# record.net
KiCad netlist of a schematic drawn in EAGLE
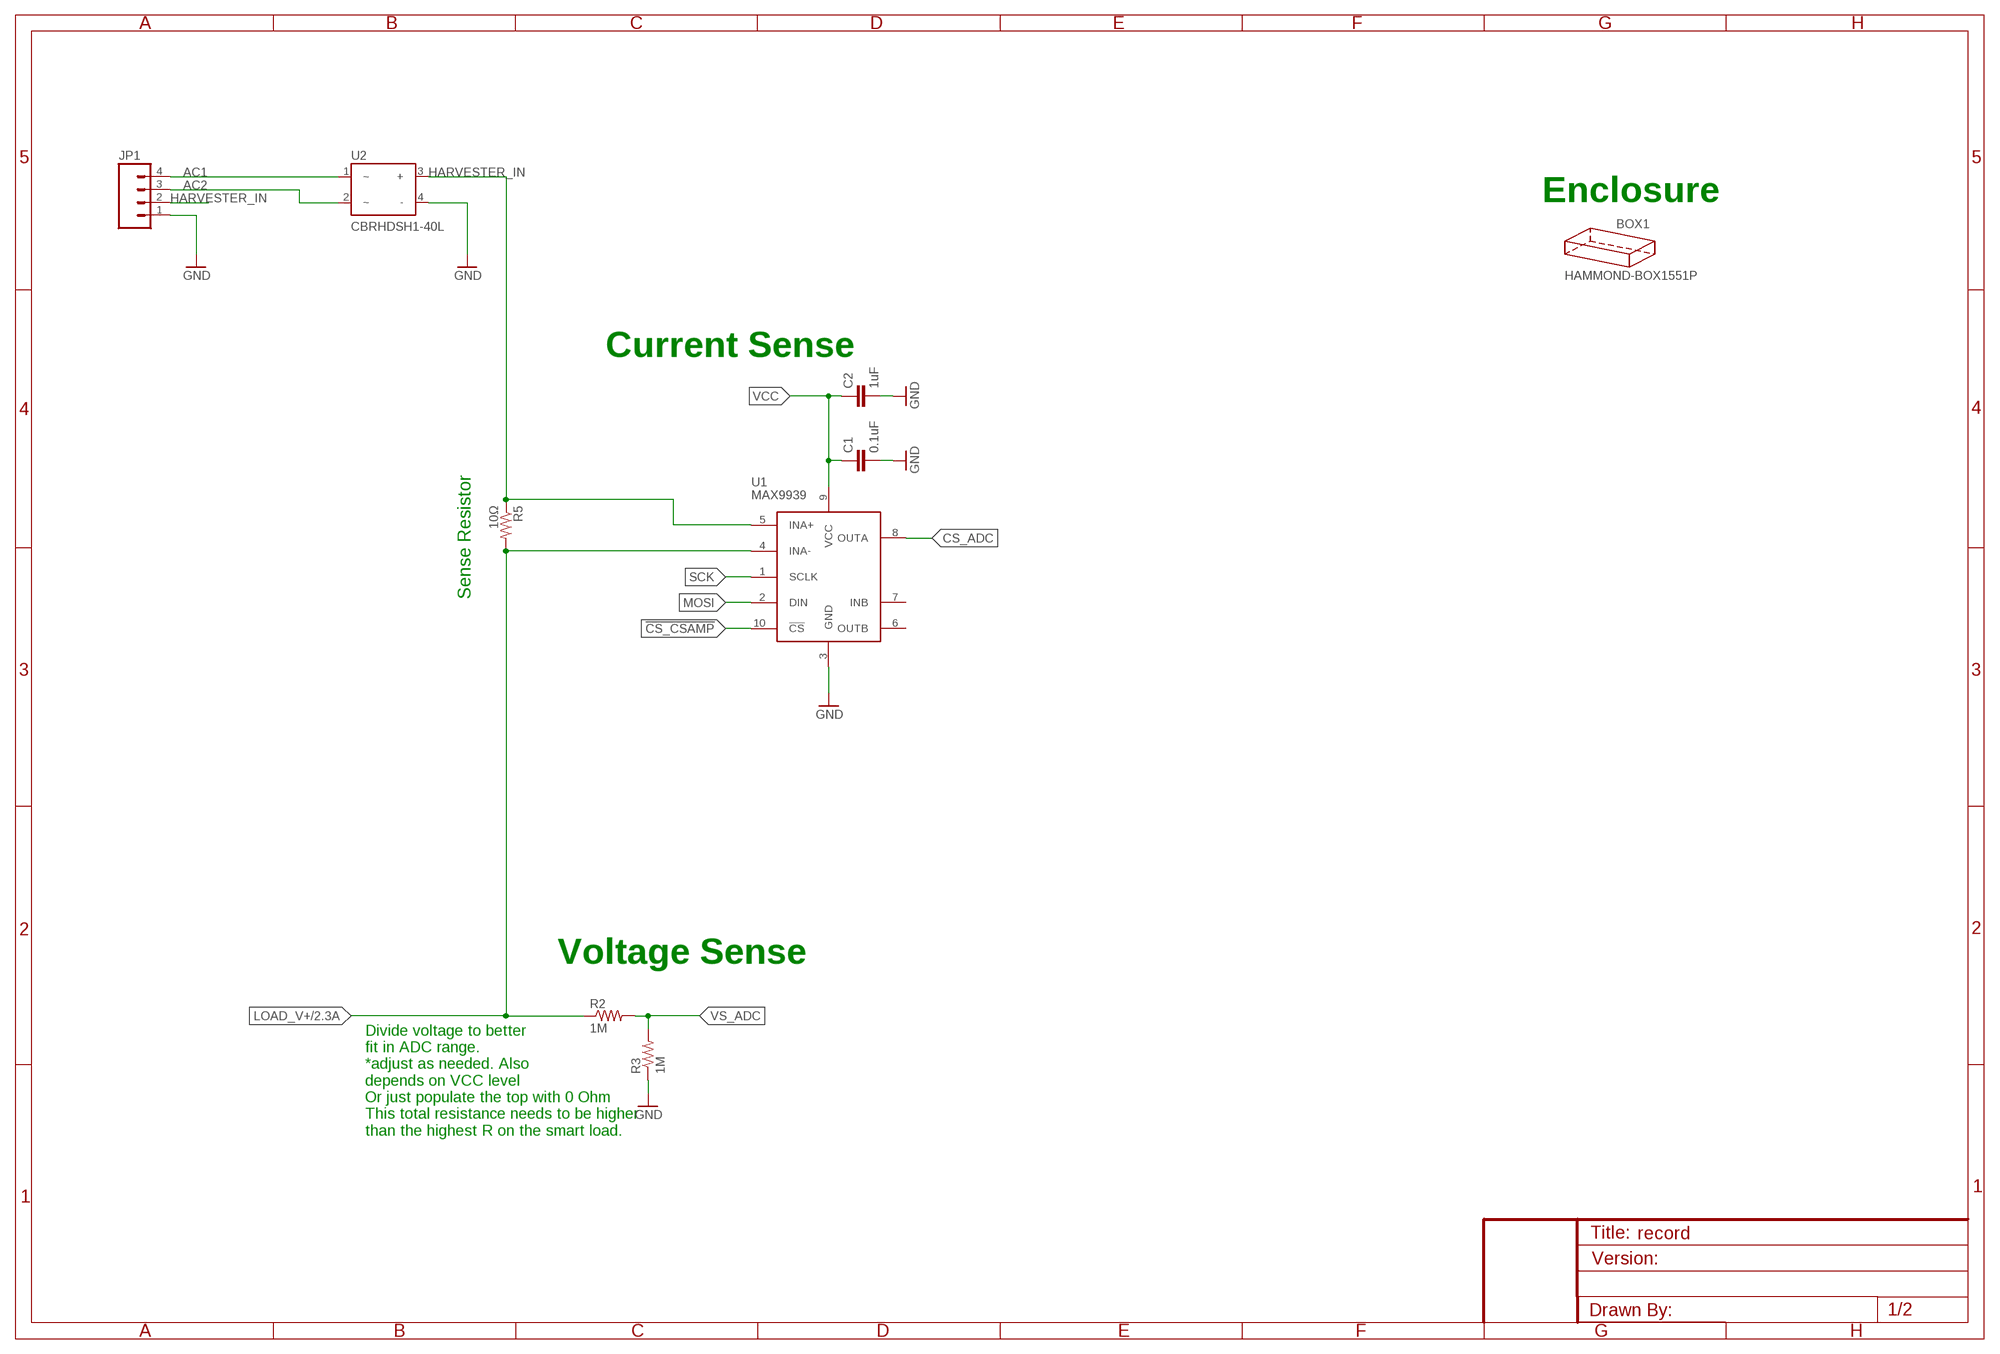
[diagram p0: schematic, sheet 1]
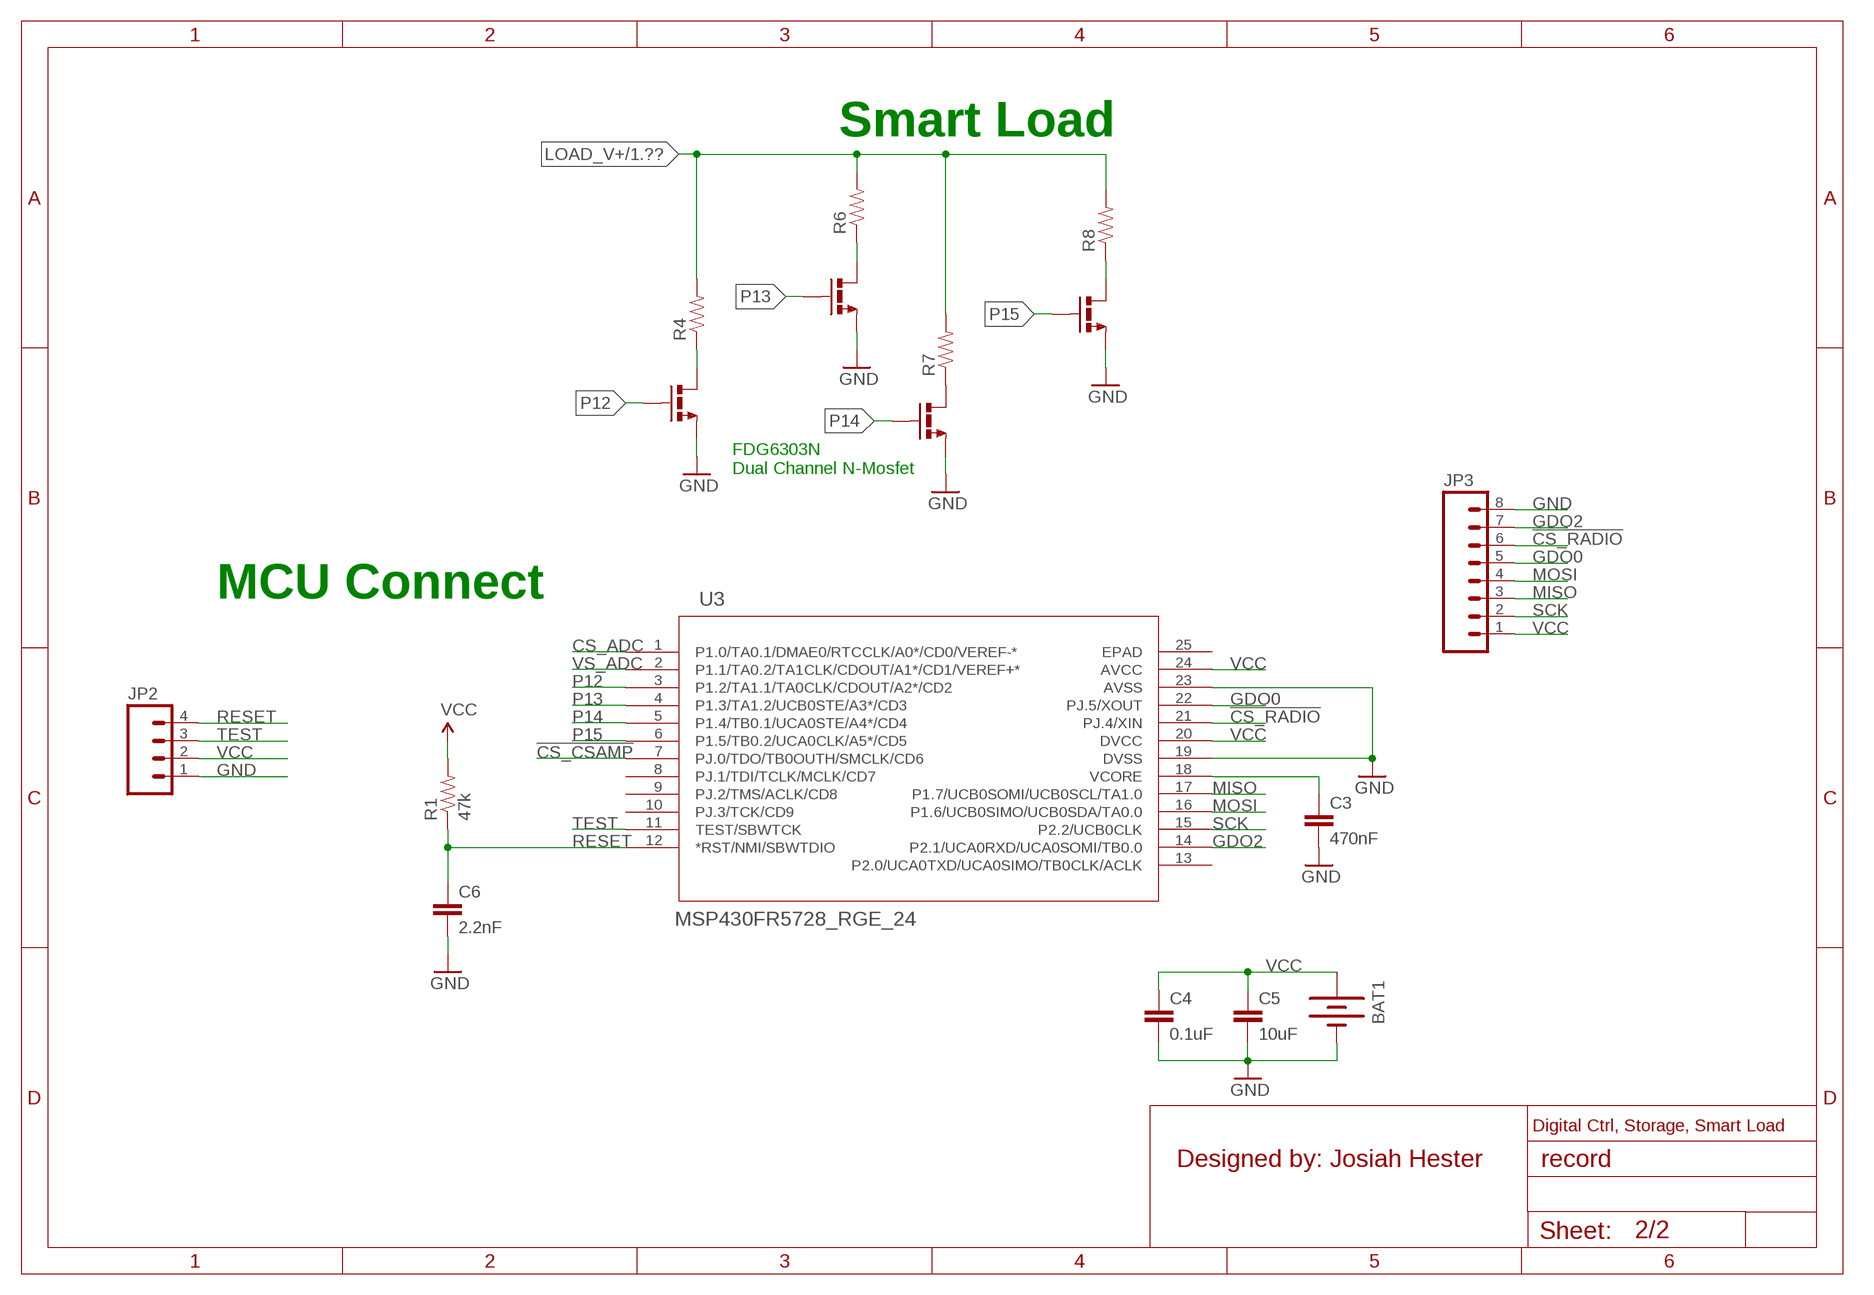
[diagram p1: schematic, sheet 2]

(export (version "E")
  (design (tool "Eeschema 10.0.6"))
  (components
    (comp (ref "BAT1")
      (value "BATTERY20PTH")
      (footprint "eagle-import:BATTCOM_20MM_PTH")
      (libsource (lib "eagle-import") (part "BATTERY20PTH"))
    )
    (comp (ref "C3")
      (value "470nF")
      (footprint "eagle-import:0805")
      (libsource (lib "eagle-import") (part "1UF-25V-10%(0805)"))
    )
    (comp (ref "C4")
      (value "0.1uF")
      (footprint "eagle-import:0805")
      (libsource (lib "eagle-import") (part "1UF-25V-10%(0805)"))
    )
    (comp (ref "C5")
      (value "10uF")
      (footprint "eagle-import:0805")
      (libsource (lib "eagle-import") (part "1UF-25V-10%(0805)"))
    )
    (comp (ref "C6")
      (value "2.2nF")
      (footprint "eagle-import:0805")
      (libsource (lib "eagle-import") (part "1UF-25V-10%(0805)"))
    )
    (comp (ref "JP2")
      (value "M04PTH")
      (footprint "eagle-import:1X04")
      (libsource (lib "eagle-import") (part "M04PTH"))
    )
    (comp (ref "JP3")
      (value "M081X08-1.27MM-PTH")
      (footprint "eagle-import:1X08-1.27MM")
      (libsource (lib "eagle-import") (part "M081X08-1.27MM-PTH"))
    )
    (comp (ref "R1")
      (value "47k")
      (footprint "eagle-import:0805")
      (libsource (lib "eagle-import") (part "0.22OHM1/4W1%(0805)"))
    )
    (comp (ref "R4")
      (value "0.22OHM1/4W1%(0805)")
      (footprint "eagle-import:0805")
      (libsource (lib "eagle-import") (part "0.22OHM1/4W1%(0805)"))
    )
    (comp (ref "R6")
      (value "0.22OHM1/4W1%(0805)")
      (footprint "eagle-import:0805")
      (libsource (lib "eagle-import") (part "0.22OHM1/4W1%(0805)"))
    )
    (comp (ref "R7")
      (value "0.22OHM1/4W1%(0805)")
      (footprint "eagle-import:0805")
      (libsource (lib "eagle-import") (part "0.22OHM1/4W1%(0805)"))
    )
    (comp (ref "R8")
      (value "0.22OHM1/4W1%(0805)")
      (footprint "eagle-import:0805")
      (libsource (lib "eagle-import") (part "0.22OHM1/4W1%(0805)"))
    )
    (comp (ref "U3")
      (value "MSP430FR5728_RGE_24")
      (footprint "eagle-import:RGE24_2P1X2P1")
      (fields
        (field (name "GENERIC_PART_NUMBER") "MSP430FR5728")
        (field (name "MANUFACTURER") "Texas Instruments")
        (field (name "MANUFACTURER_PART_NUMBER") "msp430fr5728_rge_24")
      )
      (libsource (lib "eagle-import") (part "MSP430FR5728_RGE_24"))
    )
    (comp (ref "U4")
      (value "FDG6303N")
      (footprint "eagle-import:SC70-6")
      (libsource (lib "eagle-import") (part "FDG6303N"))
    )
    (comp (ref "U5")
      (value "FDG6303N")
      (footprint "eagle-import:SC70-6")
      (libsource (lib "eagle-import") (part "FDG6303N"))
    )
    (comp (ref "BOX1")
      (value "HAMMOND-BOX1551P")
      (footprint "eagle-import:1551P")
      (libsource (lib "eagle-import") (part "HAMMOND-BOX1551P"))
    )
    (comp (ref "C1")
      (value "0.1uF")
      (footprint "eagle-import:C0805")
      (libsource (lib "eagle-import") (part "CAP0805"))
    )
    (comp (ref "C2")
      (value "1uF")
      (footprint "eagle-import:C0805")
      (libsource (lib "eagle-import") (part "CAP0805"))
    )
    (comp (ref "JP1")
      (value "M04PTH")
      (footprint "eagle-import:1X04")
      (libsource (lib "eagle-import") (part "M04PTH"))
    )
    (comp (ref "R2")
      (value "1M")
      (footprint "eagle-import:0805")
      (libsource (lib "eagle-import") (part "SparkFun-Resistors_RESISTOR0805-RES"))
    )
    (comp (ref "R3")
      (value "1M")
      (footprint "eagle-import:0805")
      (libsource (lib "eagle-import") (part "SparkFun-Resistors_RESISTOR0805-RES"))
    )
    (comp (ref "R5")
      (value "10Ω")
      (footprint "eagle-import:0805")
      (libsource (lib "eagle-import") (part "RESISTOR0805-RES"))
    )
    (comp (ref "U1")
      (value "MAX9939")
      (footprint "eagle-import:10µMAX")
      (libsource (lib "eagle-import") (part "MAX9939"))
    )
    (comp (ref "U2")
      (value "CBRHDSH1-40L")
      (footprint "eagle-import:HD_DIP4")
      (libsource (lib "eagle-import") (part "CBRHDSH1-40L"))
    )
  )
  (nets
    (net (code "1") (name "AC1") (class "Default")
      (node (ref "JP1") (pin "4") (pinfunction "4_4") (pintype "passive"))
      (node (ref "U2") (pin "1") (pinfunction "~_1") (pintype "bidirectional"))
    )
    (net (code "2") (name "AC2") (class "Default")
      (node (ref "JP1") (pin "3") (pinfunction "3_3") (pintype "passive"))
      (node (ref "U2") (pin "2") (pinfunction "~_2") (pintype "bidirectional"))
    )
    (net (code "3") (name "CS_ADC") (class "Default")
      (node (ref "U1") (pin "8") (pinfunction "OUTA_8") (pintype "bidirectional"))
      (node (ref "U3") (pin "1") (pinfunction "P1.0/TA0.1/DMAE0/RTCCLK/A0*/CD0/VEREF-*_1") (pintype "bidirectional"))
    )
    (net (code "4") (name "GDO0") (class "Default")
      (node (ref "JP3") (pin "5") (pinfunction "5_5") (pintype "passive"))
      (node (ref "U3") (pin "22") (pinfunction "PJ.5/XOUT_22") (pintype "bidirectional"))
    )
    (net (code "5") (name "GDO2") (class "Default")
      (node (ref "JP3") (pin "7") (pinfunction "7_7") (pintype "passive"))
      (node (ref "U3") (pin "14") (pinfunction "P2.1/UCA0RXD/UCA0SOMI/TB0.0_14") (pintype "bidirectional"))
    )
    (net (code "6") (name "GND") (class "Default")
      (node (ref "BAT1") (pin "2") (pinfunction "-_2") (pintype "power_in"))
      (node (ref "C1") (pin "2") (pinfunction "2_2") (pintype "passive"))
      (node (ref "C2") (pin "2") (pinfunction "2_2") (pintype "passive"))
      (node (ref "C3") (pin "2") (pinfunction "2_2") (pintype "passive"))
      (node (ref "C4") (pin "2") (pinfunction "2_2") (pintype "passive"))
      (node (ref "C5") (pin "2") (pinfunction "2_2") (pintype "passive"))
      (node (ref "C6") (pin "2") (pinfunction "2_2") (pintype "passive"))
      (node (ref "JP1") (pin "1") (pinfunction "1_1") (pintype "passive"))
      (node (ref "JP2") (pin "1") (pinfunction "1_1") (pintype "passive"))
      (node (ref "JP3") (pin "8") (pinfunction "8_8") (pintype "passive"))
      (node (ref "R3") (pin "1") (pinfunction "1_1") (pintype "passive"))
      (node (ref "U1") (pin "3") (pinfunction "GND_3") (pintype "bidirectional"))
      (node (ref "U2") (pin "4") (pinfunction "-_4") (pintype "bidirectional"))
      (node (ref "U3") (pin "19") (pinfunction "DVSS_19") (pintype "power_in"))
      (node (ref "U3") (pin "23") (pinfunction "AVSS_23") (pintype "power_in"))
      (node (ref "U4") (pin "1") (pinfunction "S2_1") (pintype "passive"))
      (node (ref "U4") (pin "4") (pinfunction "S1_4") (pintype "passive"))
      (node (ref "U5") (pin "1") (pinfunction "S2_1") (pintype "passive"))
      (node (ref "U5") (pin "4") (pinfunction "S1_4") (pintype "passive"))
    )
    (net (code "7") (name "HARVESTER_IN") (class "Default")
      (node (ref "JP1") (pin "2") (pinfunction "2_2") (pintype "passive"))
      (node (ref "R5") (pin "1") (pinfunction "1_1") (pintype "passive"))
      (node (ref "U1") (pin "5") (pinfunction "INA+_5") (pintype "bidirectional"))
      (node (ref "U2") (pin "3") (pinfunction "+_3") (pintype "bidirectional"))
    )
    (net (code "8") (name "LOAD_V+") (class "Default")
      (node (ref "R2") (pin "1") (pinfunction "1_1") (pintype "passive"))
      (node (ref "R4") (pin "2") (pinfunction "2_2") (pintype "passive"))
      (node (ref "R5") (pin "2") (pinfunction "2_2") (pintype "passive"))
      (node (ref "R6") (pin "2") (pinfunction "2_2") (pintype "passive"))
      (node (ref "R7") (pin "2") (pinfunction "2_2") (pintype "passive"))
      (node (ref "R8") (pin "2") (pinfunction "2_2") (pintype "passive"))
      (node (ref "U1") (pin "4") (pinfunction "INA-_4") (pintype "bidirectional"))
    )
    (net (code "9") (name "MISO") (class "Default")
      (node (ref "JP3") (pin "3") (pinfunction "3_3") (pintype "passive"))
      (node (ref "U3") (pin "17") (pinfunction "P1.7/UCB0SOMI/UCB0SCL/TA1.0_17") (pintype "bidirectional"))
    )
    (net (code "10") (name "MOSI") (class "Default")
      (node (ref "JP3") (pin "4") (pinfunction "4_4") (pintype "passive"))
      (node (ref "U1") (pin "2") (pinfunction "DIN_2") (pintype "bidirectional"))
      (node (ref "U3") (pin "16") (pinfunction "P1.6/UCB0SIMO/UCB0SDA/TA0.0_16") (pintype "bidirectional"))
    )
    (net (code "11") (name "Net-(U3-VCORE)") (class "Default")
      (node (ref "C3") (pin "1") (pinfunction "1_1") (pintype "passive"))
      (node (ref "U3") (pin "18") (pinfunction "VCORE_18") (pintype "power_in"))
    )
    (net (code "12") (name "Net-(U4-D1)") (class "Default")
      (node (ref "R4") (pin "1") (pinfunction "1_1") (pintype "passive"))
      (node (ref "U4") (pin "3") (pinfunction "D1_3") (pintype "passive"))
    )
    (net (code "13") (name "Net-(U4-D2)") (class "Default")
      (node (ref "R6") (pin "1") (pinfunction "1_1") (pintype "passive"))
      (node (ref "U4") (pin "6") (pinfunction "D2_6") (pintype "passive"))
    )
    (net (code "14") (name "Net-(U5-D1)") (class "Default")
      (node (ref "R7") (pin "1") (pinfunction "1_1") (pintype "passive"))
      (node (ref "U5") (pin "3") (pinfunction "D1_3") (pintype "passive"))
    )
    (net (code "15") (name "Net-(U5-D2)") (class "Default")
      (node (ref "R8") (pin "1") (pinfunction "1_1") (pintype "passive"))
      (node (ref "U5") (pin "6") (pinfunction "D2_6") (pintype "passive"))
    )
    (net (code "16") (name "P12") (class "Default")
      (node (ref "U3") (pin "3") (pinfunction "P1.2/TA1.1/TA0CLK/CDOUT/A2*/CD2_3") (pintype "bidirectional"))
      (node (ref "U4") (pin "5") (pinfunction "G1_5") (pintype "passive"))
    )
    (net (code "17") (name "P13") (class "Default")
      (node (ref "U3") (pin "4") (pinfunction "P1.3/TA1.2/UCB0STE/A3*/CD3_4") (pintype "bidirectional"))
      (node (ref "U4") (pin "2") (pinfunction "G2_2") (pintype "passive"))
    )
    (net (code "18") (name "P14") (class "Default")
      (node (ref "U3") (pin "5") (pinfunction "P1.4/TB0.1/UCA0STE/A4*/CD4_5") (pintype "bidirectional"))
      (node (ref "U5") (pin "5") (pinfunction "G1_5") (pintype "passive"))
    )
    (net (code "19") (name "P15") (class "Default")
      (node (ref "U3") (pin "6") (pinfunction "P1.5/TB0.2/UCA0CLK/A5*/CD5_6") (pintype "bidirectional"))
      (node (ref "U5") (pin "2") (pinfunction "G2_2") (pintype "passive"))
    )
    (net (code "20") (name "RESET") (class "Default")
      (node (ref "C6") (pin "1") (pinfunction "1_1") (pintype "passive"))
      (node (ref "JP2") (pin "4") (pinfunction "4_4") (pintype "passive"))
      (node (ref "R1") (pin "1") (pinfunction "1_1") (pintype "passive"))
      (node (ref "U3") (pin "12") (pinfunction "*RST/NMI/SBWTDIO_12") (pintype "bidirectional"))
    )
    (net (code "21") (name "SCK") (class "Default")
      (node (ref "JP3") (pin "2") (pinfunction "2_2") (pintype "passive"))
      (node (ref "U1") (pin "1") (pinfunction "SCLK_1") (pintype "bidirectional"))
      (node (ref "U3") (pin "15") (pinfunction "P2.2/UCB0CLK_15") (pintype "bidirectional"))
    )
    (net (code "22") (name "TEST") (class "Default")
      (node (ref "JP2") (pin "3") (pinfunction "3_3") (pintype "passive"))
      (node (ref "U3") (pin "11") (pinfunction "TEST/SBWTCK_11") (pintype "bidirectional"))
    )
    (net (code "23") (name "VCC") (class "Default")
      (node (ref "BAT1") (pin "1") (pinfunction "+_1") (pintype "power_in"))
      (node (ref "C1") (pin "1") (pinfunction "1_1") (pintype "passive"))
      (node (ref "C2") (pin "1") (pinfunction "1_1") (pintype "passive"))
      (node (ref "C4") (pin "1") (pinfunction "1_1") (pintype "passive"))
      (node (ref "C5") (pin "1") (pinfunction "1_1") (pintype "passive"))
      (node (ref "JP2") (pin "2") (pinfunction "2_2") (pintype "passive"))
      (node (ref "JP3") (pin "1") (pinfunction "1_1") (pintype "passive"))
      (node (ref "R1") (pin "2") (pinfunction "2_2") (pintype "passive"))
      (node (ref "U1") (pin "9") (pinfunction "VCC_9") (pintype "bidirectional"))
      (node (ref "U3") (pin "20") (pinfunction "DVCC_20") (pintype "power_in"))
      (node (ref "U3") (pin "24") (pinfunction "AVCC_24") (pintype "power_in"))
    )
    (net (code "24") (name "VS_ADC") (class "Default")
      (node (ref "R2") (pin "2") (pinfunction "2_2") (pintype "passive"))
      (node (ref "R3") (pin "2") (pinfunction "2_2") (pintype "passive"))
      (node (ref "U3") (pin "2") (pinfunction "P1.1/TA0.2/TA1CLK/CDOUT/A1*/CD1/VEREF+*_2") (pintype "bidirectional"))
    )
    (net (code "25") (name "unconnected-(U1-INB-Pad7)") (class "Default")
      (node (ref "U1") (pin "7") (pinfunction "INB_7") (pintype "bidirectional"))
    )
    (net (code "26") (name "unconnected-(U1-OUTB-Pad6)") (class "Default")
      (node (ref "U1") (pin "6") (pinfunction "OUTB_6") (pintype "bidirectional"))
    )
    (net (code "27") (name "unconnected-(U3-EPAD-Pad25)") (class "Default")
      (node (ref "U3") (pin "25") (pinfunction "EPAD_25") (pintype "passive"))
    )
    (net (code "28") (name "unconnected-(U3-P2.0{slash}UCA0TXD{slash}UCA0SIMO{slash}TB0CLK{slash}ACLK-Pad13)") (class "Default")
      (node (ref "U3") (pin "13") (pinfunction "P2.0/UCA0TXD/UCA0SIMO/TB0CLK/ACLK_13") (pintype "bidirectional"))
    )
    (net (code "29") (name "unconnected-(U3-PJ.1{slash}TDI{slash}TCLK{slash}MCLK{slash}CD7-Pad8)") (class "Default")
      (node (ref "U3") (pin "8") (pinfunction "PJ.1/TDI/TCLK/MCLK/CD7_8") (pintype "bidirectional"))
    )
    (net (code "30") (name "unconnected-(U3-PJ.2{slash}TMS{slash}ACLK{slash}CD8-Pad9)") (class "Default")
      (node (ref "U3") (pin "9") (pinfunction "PJ.2/TMS/ACLK/CD8_9") (pintype "bidirectional"))
    )
    (net (code "31") (name "unconnected-(U3-PJ.3{slash}TCK{slash}CD9-Pad10)") (class "Default")
      (node (ref "U3") (pin "10") (pinfunction "PJ.3/TCK/CD9_10") (pintype "bidirectional"))
    )
    (net (code "32") (name "~{CS_CSAMP}") (class "Default")
      (node (ref "U1") (pin "10") (pinfunction "~{CS}_10") (pintype "bidirectional"))
      (node (ref "U3") (pin "7") (pinfunction "PJ.0/TDO/TB0OUTH/SMCLK/CD6_7") (pintype "bidirectional"))
    )
    (net (code "33") (name "~{CS_RADIO}") (class "Default")
      (node (ref "JP3") (pin "6") (pinfunction "6_6") (pintype "passive"))
      (node (ref "U3") (pin "21") (pinfunction "PJ.4/XIN_21") (pintype "bidirectional"))
    )
  )
)
